# Power_Board_LDO.net
KiCad netlist of a schematic drawn in Altium Designer
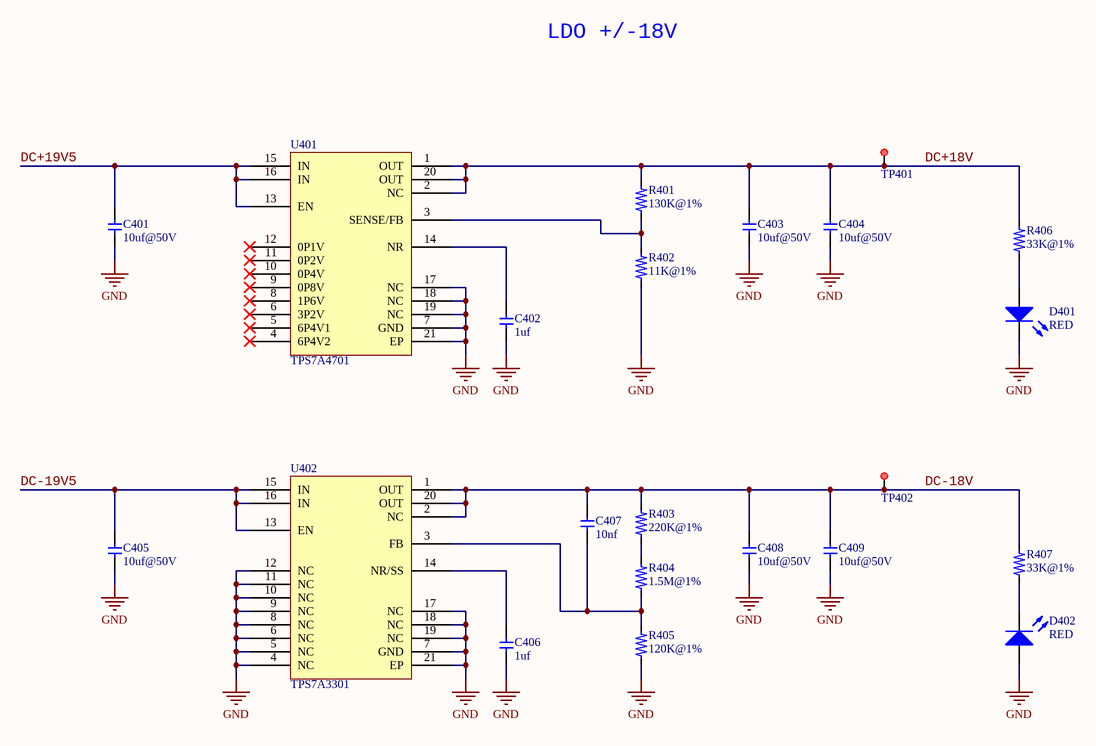
[diagram p0: Power Board.LDO.SchDoc]

(export (version "E")
  (design (tool "Eeschema 10.0.6"))
  (components
    (comp (ref "C401")
      (value "10uf@50V")
      (footprint "C1206")
      (fields (field (name "Comment") "Cap"))
      (libsource (lib "carrot_lib") (part "Cap"))
    )
    (comp (ref "C402")
      (value "1uf")
      (footprint "C0603")
      (fields (field (name "Comment") "Cap"))
      (libsource (lib "carrot_lib") (part "Cap"))
    )
    (comp (ref "C403")
      (value "10uf@50V")
      (footprint "C1206")
      (fields (field (name "Comment") "Cap"))
      (libsource (lib "carrot_lib") (part "Cap"))
    )
    (comp (ref "C404")
      (value "10uf@50V")
      (footprint "C1206")
      (fields (field (name "Comment") "Cap"))
      (libsource (lib "carrot_lib") (part "Cap"))
    )
    (comp (ref "C405")
      (value "10uf@50V")
      (footprint "C1206")
      (fields (field (name "Comment") "Cap"))
      (libsource (lib "carrot_lib") (part "Cap"))
    )
    (comp (ref "C406")
      (value "1uf")
      (footprint "C0603")
      (fields (field (name "Comment") "Cap"))
      (libsource (lib "carrot_lib") (part "Cap"))
    )
    (comp (ref "C407")
      (value "10nf")
      (footprint "C0603")
      (fields (field (name "Comment") "Cap"))
      (libsource (lib "carrot_lib") (part "Cap"))
    )
    (comp (ref "C408")
      (value "10uf@50V")
      (footprint "C1206")
      (fields (field (name "Comment") "Cap"))
      (libsource (lib "carrot_lib") (part "Cap"))
    )
    (comp (ref "C409")
      (value "10uf@50V")
      (footprint "C1206")
      (fields (field (name "Comment") "Cap"))
      (libsource (lib "carrot_lib") (part "Cap"))
    )
    (comp (ref "D401")
      (value "RED")
      (footprint "LED0603")
      (fields (field (name "Comment") "LED"))
      (libsource (lib "carrot_lib") (part "LED"))
    )
    (comp (ref "D402")
      (value "RED")
      (footprint "LED0603")
      (fields (field (name "Comment") "LED"))
      (libsource (lib "carrot_lib") (part "LED"))
    )
    (comp (ref "R401")
      (value "130K@1%")
      (footprint "R0603")
      (description "电阻")
      (fields (field (name "Comment") "Res"))
      (libsource (lib "carrot_lib") (part "Res"))
    )
    (comp (ref "R402")
      (value "11K@1%")
      (footprint "R0603")
      (description "电阻")
      (fields (field (name "Comment") "Res"))
      (libsource (lib "carrot_lib") (part "Res"))
    )
    (comp (ref "R403")
      (value "220K@1%")
      (footprint "R0603")
      (description "电阻")
      (fields (field (name "Comment") "Res"))
      (libsource (lib "carrot_lib") (part "Res"))
    )
    (comp (ref "R404")
      (value "1.5M@1%")
      (footprint "R0603")
      (description "电阻")
      (fields (field (name "Comment") "Res"))
      (libsource (lib "carrot_lib") (part "Res"))
    )
    (comp (ref "R405")
      (value "120K@1%")
      (footprint "R0603")
      (description "电阻")
      (fields (field (name "Comment") "Res"))
      (libsource (lib "carrot_lib") (part "Res"))
    )
    (comp (ref "R406")
      (value "33K@1%")
      (footprint "R0603")
      (description "电阻")
      (fields (field (name "Comment") "Res"))
      (libsource (lib "carrot_lib") (part "Res"))
    )
    (comp (ref "R407")
      (value "33K@1%")
      (footprint "R0603")
      (description "电阻")
      (fields (field (name "Comment") "Res"))
      (libsource (lib "carrot_lib") (part "Res"))
    )
    (comp (ref "TP401")
      (value "TestPoint")
      (footprint "TestPoint-THM1.0-L")
      (description "测试点")
      (libsource (lib "carrot_lib") (part "TestPoint"))
    )
    (comp (ref "TP402")
      (value "TestPoint")
      (footprint "TestPoint-THM1.0-L")
      (description "测试点")
      (libsource (lib "carrot_lib") (part "TestPoint"))
    )
    (comp (ref "U401")
      (value "TPS7A4701")
      (footprint "TPS7A4701-QFN20")
      (description "TPS7A470x 36-V, 1-A, 4-µVRMS, RF LDO Voltage Regulator")
      (libsource (lib "carrot_lib") (part "TPS7A4701"))
    )
    (comp (ref "U402")
      (value "TPS7A3301")
      (footprint "TPS7A3301-QFN20")
      (description "TPS7A33 –36-V, 1-A, Ultralow-Noise Negative Voltage Regulator")
      (libsource (lib "carrot_lib") (part "TPS7A3301"))
    )
  )
  (nets
    (net (code "1") (name "/DC+18V") (class "Default")
      (node (ref "C403") (pin "2") (pinfunction "2_2") (pintype "passive"))
      (node (ref "C404") (pin "2") (pinfunction "2_2") (pintype "passive"))
      (node (ref "R401") (pin "2") (pinfunction "2_2") (pintype "passive"))
      (node (ref "R406") (pin "2") (pinfunction "2_2") (pintype "passive"))
      (node (ref "TP401") (pin "1") (pinfunction "1_1") (pintype "passive"))
      (node (ref "U401") (pin "1") (pinfunction "OUT_1") (pintype "passive"))
      (node (ref "U401") (pin "2") (pinfunction "NC_2") (pintype "passive"))
      (node (ref "U401") (pin "20") (pinfunction "OUT_20") (pintype "passive"))
    )
    (net (code "2") (name "/DC+19V5") (class "Default")
      (node (ref "C401") (pin "2") (pinfunction "2_2") (pintype "passive"))
      (node (ref "U401") (pin "13") (pinfunction "EN_13") (pintype "passive"))
      (node (ref "U401") (pin "15") (pinfunction "IN_15") (pintype "passive"))
      (node (ref "U401") (pin "16") (pinfunction "IN_16") (pintype "passive"))
    )
    (net (code "3") (name "/DC-18V") (class "Default")
      (node (ref "C407") (pin "2") (pinfunction "2_2") (pintype "passive"))
      (node (ref "C408") (pin "2") (pinfunction "2_2") (pintype "passive"))
      (node (ref "C409") (pin "2") (pinfunction "2_2") (pintype "passive"))
      (node (ref "R403") (pin "2") (pinfunction "2_2") (pintype "passive"))
      (node (ref "R407") (pin "2") (pinfunction "2_2") (pintype "passive"))
      (node (ref "TP402") (pin "1") (pinfunction "1_1") (pintype "passive"))
      (node (ref "U402") (pin "1") (pinfunction "OUT_1") (pintype "passive"))
      (node (ref "U402") (pin "2") (pinfunction "NC_2") (pintype "passive"))
      (node (ref "U402") (pin "20") (pinfunction "OUT_20") (pintype "passive"))
    )
    (net (code "4") (name "/DC-19V5") (class "Default")
      (node (ref "C405") (pin "2") (pinfunction "2_2") (pintype "passive"))
      (node (ref "U402") (pin "13") (pinfunction "EN_13") (pintype "passive"))
      (node (ref "U402") (pin "15") (pinfunction "IN_15") (pintype "passive"))
      (node (ref "U402") (pin "16") (pinfunction "IN_16") (pintype "passive"))
    )
    (net (code "5") (name "GND") (class "Default")
      (node (ref "C401") (pin "1") (pinfunction "1_1") (pintype "passive"))
      (node (ref "C402") (pin "2") (pinfunction "2_2") (pintype "passive"))
      (node (ref "C403") (pin "1") (pinfunction "1_1") (pintype "passive"))
      (node (ref "C404") (pin "1") (pinfunction "1_1") (pintype "passive"))
      (node (ref "C405") (pin "1") (pinfunction "1_1") (pintype "passive"))
      (node (ref "C406") (pin "2") (pinfunction "2_2") (pintype "passive"))
      (node (ref "C408") (pin "1") (pinfunction "1_1") (pintype "passive"))
      (node (ref "C409") (pin "1") (pinfunction "1_1") (pintype "passive"))
      (node (ref "D401") (pin "2") (pinfunction "K_2") (pintype "passive"))
      (node (ref "D402") (pin "1") (pinfunction "A_1") (pintype "passive"))
      (node (ref "R402") (pin "1") (pinfunction "1_1") (pintype "passive"))
      (node (ref "R405") (pin "1") (pinfunction "1_1") (pintype "passive"))
      (node (ref "U401") (pin "17") (pinfunction "NC_17") (pintype "passive"))
      (node (ref "U401") (pin "18") (pinfunction "NC_18") (pintype "passive"))
      (node (ref "U401") (pin "19") (pinfunction "NC_19") (pintype "passive"))
      (node (ref "U401") (pin "21") (pinfunction "EP_21") (pintype "passive"))
      (node (ref "U401") (pin "7") (pinfunction "GND_7") (pintype "passive"))
      (node (ref "U402") (pin "10") (pinfunction "NC_10") (pintype "passive"))
      (node (ref "U402") (pin "11") (pinfunction "NC_11") (pintype "passive"))
      (node (ref "U402") (pin "12") (pinfunction "NC_12") (pintype "passive"))
      (node (ref "U402") (pin "17") (pinfunction "NC_17") (pintype "passive"))
      (node (ref "U402") (pin "18") (pinfunction "NC_18") (pintype "passive"))
      (node (ref "U402") (pin "19") (pinfunction "NC_19") (pintype "passive"))
      (node (ref "U402") (pin "21") (pinfunction "EP_21") (pintype "passive"))
      (node (ref "U402") (pin "4") (pinfunction "NC_4") (pintype "passive"))
      (node (ref "U402") (pin "5") (pinfunction "NC_5") (pintype "passive"))
      (node (ref "U402") (pin "6") (pinfunction "NC_6") (pintype "passive"))
      (node (ref "U402") (pin "7") (pinfunction "GND_7") (pintype "passive"))
      (node (ref "U402") (pin "8") (pinfunction "NC_8") (pintype "passive"))
      (node (ref "U402") (pin "9") (pinfunction "NC_9") (pintype "passive"))
    )
    (net (code "6") (name "Net-(D401-A)") (class "Default")
      (node (ref "D401") (pin "1") (pinfunction "A_1") (pintype "passive"))
      (node (ref "R406") (pin "1") (pinfunction "1_1") (pintype "passive"))
    )
    (net (code "7") (name "Net-(D402-K)") (class "Default")
      (node (ref "D402") (pin "2") (pinfunction "K_2") (pintype "passive"))
      (node (ref "R407") (pin "1") (pinfunction "1_1") (pintype "passive"))
    )
    (net (code "8") (name "Net-(R403-Pad1)") (class "Default")
      (node (ref "R403") (pin "1") (pinfunction "1_1") (pintype "passive"))
      (node (ref "R404") (pin "2") (pinfunction "2_2") (pintype "passive"))
    )
    (net (code "9") (name "Net-(U401-NR)") (class "Default")
      (node (ref "C402") (pin "1") (pinfunction "1_1") (pintype "passive"))
      (node (ref "U401") (pin "14") (pinfunction "NR_14") (pintype "passive"))
    )
    (net (code "10") (name "Net-(U401-SENSE{slash}FB)") (class "Default")
      (node (ref "R401") (pin "1") (pinfunction "1_1") (pintype "passive"))
      (node (ref "R402") (pin "2") (pinfunction "2_2") (pintype "passive"))
      (node (ref "U401") (pin "3") (pinfunction "SENSE/FB_3") (pintype "passive"))
    )
    (net (code "11") (name "Net-(U402-FB)") (class "Default")
      (node (ref "C407") (pin "1") (pinfunction "1_1") (pintype "passive"))
      (node (ref "R404") (pin "1") (pinfunction "1_1") (pintype "passive"))
      (node (ref "R405") (pin "2") (pinfunction "2_2") (pintype "passive"))
      (node (ref "U402") (pin "3") (pinfunction "FB_3") (pintype "passive"))
    )
    (net (code "12") (name "Net-(U402-NR{slash}SS)") (class "Default")
      (node (ref "C406") (pin "1") (pinfunction "1_1") (pintype "passive"))
      (node (ref "U402") (pin "14") (pinfunction "NR/SS_14") (pintype "passive"))
    )
    (net (code "13") (name "unconnected-(U401-0P1V-Pad12)") (class "Default")
      (node (ref "U401") (pin "12") (pinfunction "0P1V_12") (pintype "passive+no_connect"))
    )
    (net (code "14") (name "unconnected-(U401-0P2V-Pad11)") (class "Default")
      (node (ref "U401") (pin "11") (pinfunction "0P2V_11") (pintype "passive+no_connect"))
    )
    (net (code "15") (name "unconnected-(U401-0P4V-Pad10)") (class "Default")
      (node (ref "U401") (pin "10") (pinfunction "0P4V_10") (pintype "passive+no_connect"))
    )
    (net (code "16") (name "unconnected-(U401-0P8V-Pad9)") (class "Default")
      (node (ref "U401") (pin "9") (pinfunction "0P8V_9") (pintype "passive+no_connect"))
    )
    (net (code "17") (name "unconnected-(U401-1P6V-Pad8)") (class "Default")
      (node (ref "U401") (pin "8") (pinfunction "1P6V_8") (pintype "passive+no_connect"))
    )
    (net (code "18") (name "unconnected-(U401-3P2V-Pad6)") (class "Default")
      (node (ref "U401") (pin "6") (pinfunction "3P2V_6") (pintype "passive+no_connect"))
    )
    (net (code "19") (name "unconnected-(U401-6P4V1-Pad5)") (class "Default")
      (node (ref "U401") (pin "5") (pinfunction "6P4V1_5") (pintype "passive+no_connect"))
    )
    (net (code "20") (name "unconnected-(U401-6P4V2-Pad4)") (class "Default")
      (node (ref "U401") (pin "4") (pinfunction "6P4V2_4") (pintype "passive+no_connect"))
    )
  )
)
